# SD_CARD.net
KiCad netlist of a schematic drawn in Altium Designer
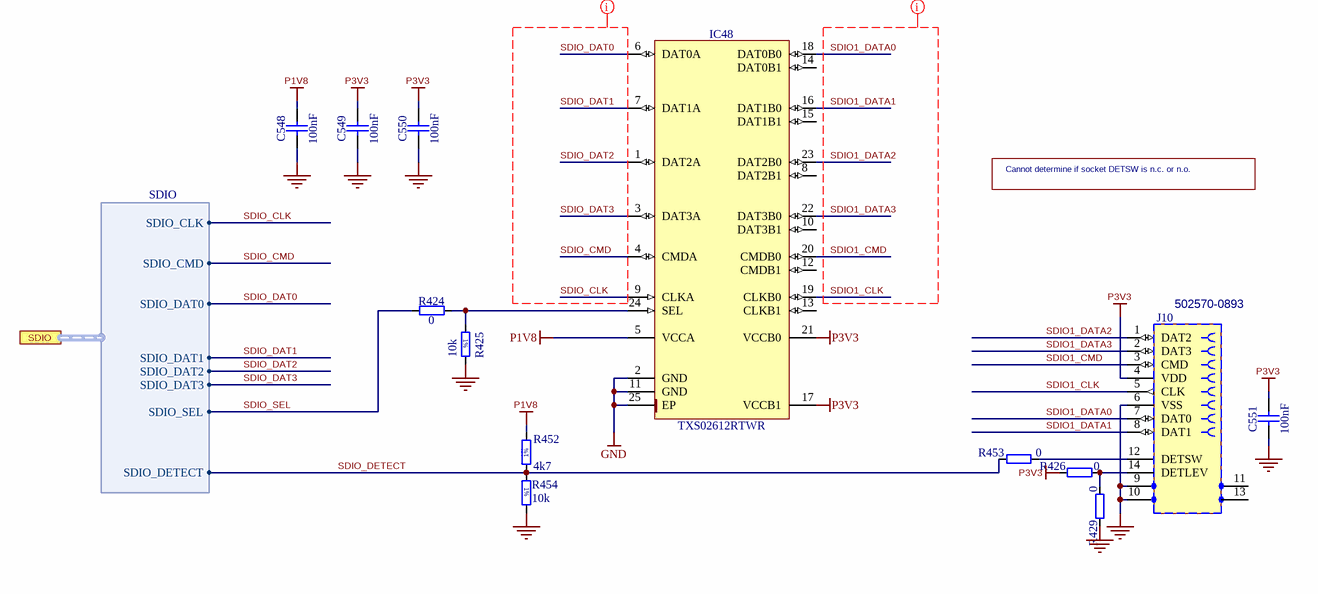
[diagram p0: SD_CARD.SchDoc]

(export (version "E")
  (design (tool "Eeschema 10.0.6"))
  (components
    (comp (ref "C548")
      (value "100nF")
      (footprint "CAPC0603X33N")
      (description "Non-polarised capacitor")
      (fields
        (field (name "MANUFACTURER PART NUMBER") "CC0201_100NF_6.3V_10%_X5R")
        (field (name "MANUFACTURER") "GENERIC")
        (field (name "AUTHOR") "CERN DEM JLC")
      )
      (libsource (lib "Capacitors") (part "Capacitor - non polarized"))
    )
    (comp (ref "C549")
      (value "100nF")
      (footprint "CAPC0603X33N")
      (description "Non-polarised capacitor")
      (fields
        (field (name "MANUFACTURER PART NUMBER") "CC0201_100NF_6.3V_10%_X5R")
        (field (name "MANUFACTURER") "GENERIC")
        (field (name "AUTHOR") "CERN DEM JLC")
      )
      (libsource (lib "Capacitors") (part "Capacitor - non polarized"))
    )
    (comp (ref "C550")
      (value "100nF")
      (footprint "CAPC0603X33N")
      (description "Non-polarised capacitor")
      (fields
        (field (name "MANUFACTURER PART NUMBER") "CC0201_100NF_6.3V_10%_X5R")
        (field (name "MANUFACTURER") "GENERIC")
        (field (name "AUTHOR") "CERN DEM JLC")
      )
      (libsource (lib "Capacitors") (part "Capacitor - non polarized"))
    )
    (comp (ref "C551")
      (value "100nF")
      (footprint "CAPC0603X33N")
      (description "Non-polarised capacitor")
      (fields
        (field (name "MANUFACTURER PART NUMBER") "CC0201_100NF_6.3V_10%_X5R")
        (field (name "MANUFACTURER") "GENERIC")
        (field (name "AUTHOR") "CERN DEM JLC")
      )
      (libsource (lib "Capacitors") (part "Capacitor - non polarized"))
    )
    (comp (ref "IC48")
      (value "TXS02612RTWR")
      (footprint "QFN50P400X400X80-25N-S255")
      (description "SDIO Port Expander With Voltage-Level Translation")
      (fields (field (name "MANUFACTURER") "TEXAS INSTRUMENTS") (field (name "AUTHOR") "CERN DEM JLC"))
      (libsource (lib "ICs And Semiconductors") (part "TXS02612RTWR"))
    )
    (comp (ref "J10")
      (value "microSD")
      (footprint "MOLEX_502570-0893")
      (description "Connector MicroSD 8 Pin")
      (fields
        (field (name "MANUFACTURER PART NUMBER") "502570-0893")
        (field (name "MANUFACTURER") "MOLEX")
        (field (name "PART NUMBER") "MOLEX_502570-0893")
        (field (name "AUTHOR") "CERN DEM JLC")
      )
      (libsource (lib "Connectors") (part "MOLEX_502570-0893"))
    )
    (comp (ref "R424")
      (value "0")
      (footprint "RESC1005X40N")
      (description "Resistor")
      (fields
        (field (name "PART NUMBER") "R0402_0R_JUMPER")
        (field (name "MANUFACTURER") "GENERIC")
        (field (name "AUTHOR") "CERN DEM JLC")
      )
      (libsource (lib "Resistors") (part "Resistor"))
    )
    (comp (ref "R425")
      (value "10k")
      (footprint "RESC1005X40N")
      (description "Resistor - 1%")
      (fields
        (field (name "MANUFACTURER PART NUMBER") "R0402_10K_1%_0.0625W_100PPM")
        (field (name "MANUFACTURER") "GENERIC")
        (field (name "AUTHOR") "CERN DEM JLC")
      )
      (libsource (lib "Resistors") (part "Resistor - 1%"))
    )
    (comp (ref "R426")
      (value "0")
      (footprint "RESC1005X40N")
      (description "Resistor")
      (fields
        (field (name "MANUFACTURER PART NUMBER") "R0402_0R_JUMPER")
        (field (name "MANUFACTURER") "GENERIC")
        (field (name "AUTHOR") "CERN DEM JLC")
      )
      (libsource (lib "Resistors") (part "Resistor"))
    )
    (comp (ref "R429")
      (value "0")
      (footprint "RESC1005X40N")
      (description "Resistor")
      (fields
        (field (name "MANUFACTURER PART NUMBER") "R0402_0R_JUMPER")
        (field (name "MANUFACTURER") "GENERIC")
        (field (name "AUTHOR") "CERN DEM JLC")
      )
      (libsource (lib "Resistors") (part "Resistor"))
    )
    (comp (ref "R452")
      (value "4k7")
      (footprint "RESC1005X40N")
      (description "Resistor - 1%")
      (fields
        (field (name "MANUFACTURER PART NUMBER") "R0402_4K7_1%_0.0625W_100PPM")
        (field (name "MANUFACTURER") "GENERIC")
        (field (name "AUTHOR") "CERN DEM JLC")
      )
      (libsource (lib "Resistors") (part "Resistor - 1%"))
    )
    (comp (ref "R453")
      (value "0")
      (footprint "RESC1005X40N")
      (description "Resistor")
      (fields
        (field (name "MANUFACTURER PART NUMBER") "R0402_0R_JUMPER")
        (field (name "MANUFACTURER") "GENERIC")
        (field (name "AUTHOR") "CERN DEM JLC")
      )
      (libsource (lib "Resistors") (part "Resistor"))
    )
    (comp (ref "R454")
      (value "10k")
      (footprint "RESC1005X40N")
      (description "Resistor - 1%")
      (fields
        (field (name "PART NUMBER") "R0402_10K_1%_0.0625W_100PPM")
        (field (name "POWER") "0.0625W")
        (field (name "AUTHOR") "CERN DEM JLC")
      )
      (libsource (lib "Resistors") (part "Resistor - 1%"))
    )
  )
  (nets
    (net (code "2") (name "/SDIO1_CLK") (class "Default")
      (node (ref "IC48") (pin "19") (pinfunction "CLKB0_19") (pintype "bidirectional"))
      (node (ref "J10") (pin "5") (pinfunction "CLK_5") (pintype "output"))
    )
    (net (code "3") (name "/SDIO1_CMD") (class "Default")
      (node (ref "IC48") (pin "20") (pinfunction "CMDB0_20") (pintype "bidirectional"))
      (node (ref "J10") (pin "3") (pinfunction "CMD_3") (pintype "bidirectional"))
    )
    (net (code "4") (name "/SDIO1_DATA0") (class "Default")
      (node (ref "IC48") (pin "18") (pinfunction "DAT0B0_18") (pintype "bidirectional"))
      (node (ref "J10") (pin "7") (pinfunction "DAT0_7") (pintype "bidirectional"))
    )
    (net (code "5") (name "/SDIO1_DATA1") (class "Default")
      (node (ref "IC48") (pin "16") (pinfunction "DAT1B0_16") (pintype "bidirectional"))
      (node (ref "J10") (pin "8") (pinfunction "DAT1_8") (pintype "bidirectional"))
    )
    (net (code "6") (name "/SDIO1_DATA2") (class "Default")
      (node (ref "IC48") (pin "23") (pinfunction "DAT2B0_23") (pintype "bidirectional"))
      (node (ref "J10") (pin "1") (pinfunction "DAT2_1") (pintype "bidirectional"))
    )
    (net (code "7") (name "/SDIO1_DATA3") (class "Default")
      (node (ref "IC48") (pin "22") (pinfunction "DAT3B0_22") (pintype "bidirectional"))
      (node (ref "J10") (pin "2") (pinfunction "DAT3_2") (pintype "bidirectional"))
    )
    (net (code "8") (name "/SDIO_CLK") (class "Default")
      (node (ref "IC48") (pin "9") (pinfunction "CLKA_9") (pintype "input"))
    )
    (net (code "9") (name "/SDIO_CMD") (class "Default")
      (node (ref "IC48") (pin "4") (pinfunction "CMDA_4") (pintype "bidirectional"))
    )
    (net (code "10") (name "/SDIO_DAT0") (class "Default")
      (node (ref "IC48") (pin "6") (pinfunction "DAT0A_6") (pintype "bidirectional"))
    )
    (net (code "11") (name "/SDIO_DAT1") (class "Default")
      (node (ref "IC48") (pin "7") (pinfunction "DAT1A_7") (pintype "bidirectional"))
    )
    (net (code "12") (name "/SDIO_DAT2") (class "Default")
      (node (ref "IC48") (pin "1") (pinfunction "DAT2A_1") (pintype "bidirectional"))
    )
    (net (code "13") (name "/SDIO_DAT3") (class "Default")
      (node (ref "IC48") (pin "3") (pinfunction "DAT3A_3") (pintype "bidirectional"))
    )
    (net (code "14") (name "/SDIO_DETECT") (class "Default")
      (node (ref "R452") (pin "1") (pinfunction "1_1") (pintype "passive"))
      (node (ref "R453") (pin "1") (pinfunction "1_1") (pintype "passive"))
      (node (ref "R454") (pin "1") (pinfunction "1_1") (pintype "passive"))
    )
    (net (code "15") (name "/SDIO_SEL") (class "Default")
      (node (ref "R424") (pin "1") (pinfunction "1_1") (pintype "passive"))
    )
    (net (code "17") (name "GND") (class "Default")
      (node (ref "C548") (pin "2") (pinfunction "2_2") (pintype "passive"))
      (node (ref "C549") (pin "2") (pinfunction "2_2") (pintype "passive"))
      (node (ref "C550") (pin "2") (pinfunction "2_2") (pintype "passive"))
      (node (ref "C551") (pin "2") (pinfunction "2_2") (pintype "passive"))
      (node (ref "IC48") (pin "11") (pinfunction "GND_11") (pintype "power_in"))
      (node (ref "IC48") (pin "2") (pinfunction "GND_2") (pintype "power_in"))
      (node (ref "IC48") (pin "25") (pinfunction "EP_25") (pintype "power_in"))
      (node (ref "J10") (pin "10") (pinfunction "10_10") (pintype "passive"))
      (node (ref "J10") (pin "6") (pinfunction "VSS_6") (pintype "power_in"))
      (node (ref "J10") (pin "9") (pinfunction "9_9") (pintype "passive"))
      (node (ref "R425") (pin "2") (pinfunction "2_2") (pintype "passive"))
      (node (ref "R429") (pin "1") (pinfunction "1_1") (pintype "passive"))
      (node (ref "R454") (pin "2") (pinfunction "2_2") (pintype "passive"))
    )
    (net (code "18") (name "Net-(IC48-SEL)") (class "Default")
      (node (ref "IC48") (pin "24") (pinfunction "SEL_24") (pintype "input"))
      (node (ref "R424") (pin "2") (pinfunction "2_2") (pintype "passive"))
      (node (ref "R425") (pin "1") (pinfunction "1_1") (pintype "passive"))
    )
    (net (code "19") (name "Net-(J10-DETLEV)") (class "Default")
      (node (ref "J10") (pin "14") (pinfunction "DETLEV_14") (pintype "passive"))
      (node (ref "R426") (pin "2") (pinfunction "2_2") (pintype "passive"))
      (node (ref "R429") (pin "2") (pinfunction "2_2") (pintype "passive"))
    )
    (net (code "20") (name "Net-(J10-DETSW)") (class "Default")
      (node (ref "J10") (pin "12") (pinfunction "DETSW_12") (pintype "passive"))
      (node (ref "R453") (pin "2") (pinfunction "2_2") (pintype "passive"))
    )
    (net (code "21") (name "P1V8") (class "Default")
      (node (ref "C548") (pin "1") (pinfunction "1_1") (pintype "passive"))
      (node (ref "IC48") (pin "5") (pinfunction "VCCA_5") (pintype "power_in"))
      (node (ref "R452") (pin "2") (pinfunction "2_2") (pintype "passive"))
    )
    (net (code "22") (name "P3V3") (class "Default")
      (node (ref "C549") (pin "1") (pinfunction "1_1") (pintype "passive"))
      (node (ref "C550") (pin "1") (pinfunction "1_1") (pintype "passive"))
      (node (ref "C551") (pin "1") (pinfunction "1_1") (pintype "passive"))
      (node (ref "IC48") (pin "17") (pinfunction "VCCB1_17") (pintype "power_in"))
      (node (ref "IC48") (pin "21") (pinfunction "VCCB0_21") (pintype "power_in"))
      (node (ref "J10") (pin "4") (pinfunction "VDD_4") (pintype "power_in"))
      (node (ref "R426") (pin "1") (pinfunction "1_1") (pintype "passive"))
    )
    (net (code "23") (name "unconnected-(IC48-CLKB1-Pad13)") (class "Default")
      (node (ref "IC48") (pin "13") (pinfunction "CLKB1_13") (pintype "bidirectional"))
    )
    (net (code "24") (name "unconnected-(IC48-CMDB1-Pad12)") (class "Default")
      (node (ref "IC48") (pin "12") (pinfunction "CMDB1_12") (pintype "bidirectional"))
    )
    (net (code "25") (name "unconnected-(IC48-DAT0B1-Pad14)") (class "Default")
      (node (ref "IC48") (pin "14") (pinfunction "DAT0B1_14") (pintype "bidirectional"))
    )
    (net (code "26") (name "unconnected-(IC48-DAT1B1-Pad15)") (class "Default")
      (node (ref "IC48") (pin "15") (pinfunction "DAT1B1_15") (pintype "bidirectional"))
    )
    (net (code "27") (name "unconnected-(IC48-DAT2B1-Pad8)") (class "Default")
      (node (ref "IC48") (pin "8") (pinfunction "DAT2B1_8") (pintype "bidirectional"))
    )
    (net (code "28") (name "unconnected-(IC48-DAT3B1-Pad10)") (class "Default")
      (node (ref "IC48") (pin "10") (pinfunction "DAT3B1_10") (pintype "bidirectional"))
    )
    (net (code "29") (name "unconnected-(J10-Pad11)") (class "Default")
      (node (ref "J10") (pin "11") (pinfunction "11_11") (pintype "passive"))
    )
    (net (code "30") (name "unconnected-(J10-Pad13)") (class "Default")
      (node (ref "J10") (pin "13") (pinfunction "13_13") (pintype "passive"))
    )
  )
)
